# SUP_1V.net
KiCad netlist of a schematic drawn in Altium Designer
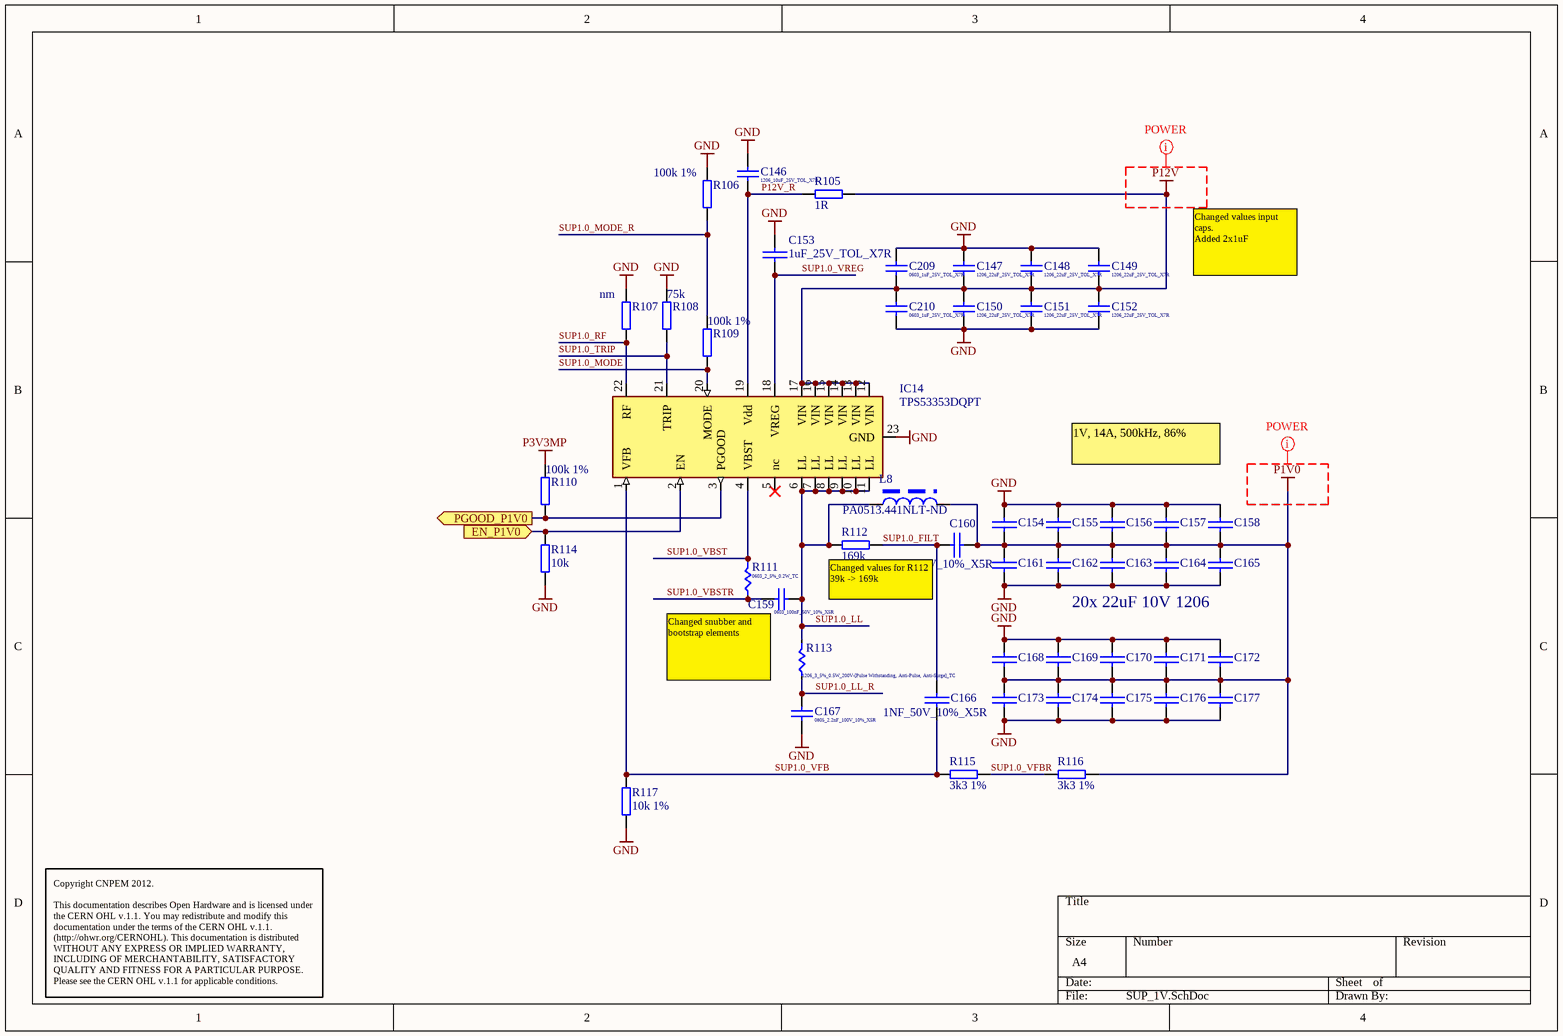
[diagram p0: SUP_1V.SchDoc]

(export (version "E")
  (design (tool "Eeschema 10.0.6"))
  (components
    (comp (ref "C146")
      (value "1206_10uF_25V_TOL_X7R")
      (footprint "CAPC3225X140N")
      (fields (field (name "PART NUMBER") "Ceramic_1206"))
      (libsource (lib "Capacitors") (part "Capacitor"))
    )
    (comp (ref "C147")
      (value "1206_22uF_25V_TOL_X7R")
      (footprint "CAPC3225X140N")
      (fields (field (name "PART NUMBER") "Ceramic_1206"))
      (libsource (lib "Capacitors") (part "Capacitor"))
    )
    (comp (ref "C148")
      (value "1206_22uF_25V_TOL_X7R")
      (footprint "CAPC3225X140N")
      (fields (field (name "PART NUMBER") "Ceramic_1206"))
      (libsource (lib "Capacitors") (part "Capacitor"))
    )
    (comp (ref "C149")
      (value "1206_22uF_25V_TOL_X7R")
      (footprint "CAPC3225X140N")
      (fields (field (name "PART NUMBER") "Ceramic_1206"))
      (libsource (lib "Capacitors") (part "Capacitor"))
    )
    (comp (ref "C150")
      (value "1206_22uF_25V_TOL_X7R")
      (footprint "CAPC3225X140N")
      (fields (field (name "PART NUMBER") "Ceramic_1206"))
      (libsource (lib "Capacitors") (part "Capacitor"))
    )
    (comp (ref "C151")
      (value "1206_22uF_25V_TOL_X7R")
      (footprint "CAPC3225X140N")
      (fields (field (name "PART NUMBER") "Ceramic_1206"))
      (libsource (lib "Capacitors") (part "Capacitor"))
    )
    (comp (ref "C152")
      (value "1206_22uF_25V_TOL_X7R")
      (footprint "CAPC3225X140N")
      (fields (field (name "PART NUMBER") "Ceramic_1206"))
      (libsource (lib "Capacitors") (part "Capacitor"))
    )
    (comp (ref "C153")
      (value "1uF_25V_TOL_X7R")
      (footprint "0603C")
      (description "Capacitor SMD")
      (libsource (lib "LIBRARY_SCH") (part "CAP_SMD_0603"))
    )
    (comp (ref "C154")
      (value "22UF_10V_10%_X7R")
      (footprint "1206C")
      (description "Capacitor SMD")
      (libsource (lib "LIBRARY_SCH") (part "CAP_SMD_1206"))
    )
    (comp (ref "C155")
      (value "22UF_10V_10%_X7R")
      (footprint "1206C")
      (description "Capacitor SMD")
      (libsource (lib "LIBRARY_SCH") (part "CAP_SMD_1206"))
    )
    (comp (ref "C156")
      (value "22UF_10V_10%_X7R")
      (footprint "1206C")
      (description "Capacitor SMD")
      (libsource (lib "LIBRARY_SCH") (part "CAP_SMD_1206"))
    )
    (comp (ref "C157")
      (value "22UF_10V_10%_X7R")
      (footprint "1206C")
      (description "Capacitor SMD")
      (libsource (lib "LIBRARY_SCH") (part "CAP_SMD_1206"))
    )
    (comp (ref "C158")
      (value "22UF_10V_10%_X7R")
      (footprint "1206C")
      (description "Capacitor SMD")
      (libsource (lib "LIBRARY_SCH") (part "CAP_SMD_1206"))
    )
    (comp (ref "C159")
      (value "0603_100nF_50V_10%_X5R")
      (footprint "CAPC1608X90N")
      (fields (field (name "PART NUMBER") "Ceramic_0603"))
      (libsource (lib "Capacitors") (part "Capacitor"))
    )
    (comp (ref "C160")
      (value "22NF_50V_10%_X5R")
      (footprint "0402C")
      (description "Capacitor SMD")
      (libsource (lib "LIBRARY_SCH") (part "CAP_SMD_0402"))
    )
    (comp (ref "C161")
      (value "22UF_10V_10%_X7R")
      (footprint "1206C")
      (description "Capacitor SMD")
      (libsource (lib "LIBRARY_SCH") (part "CAP_SMD_1206"))
    )
    (comp (ref "C162")
      (value "22UF_10V_10%_X7R")
      (footprint "1206C")
      (description "Capacitor SMD")
      (libsource (lib "LIBRARY_SCH") (part "CAP_SMD_1206"))
    )
    (comp (ref "C163")
      (value "22UF_10V_10%_X7R")
      (footprint "1206C")
      (description "Capacitor SMD")
      (libsource (lib "LIBRARY_SCH") (part "CAP_SMD_1206"))
    )
    (comp (ref "C164")
      (value "22UF_10V_10%_X7R")
      (footprint "1206C")
      (description "Capacitor SMD")
      (libsource (lib "LIBRARY_SCH") (part "CAP_SMD_1206"))
    )
    (comp (ref "C165")
      (value "22UF_10V_10%_X7R")
      (footprint "1206C")
      (description "Capacitor SMD")
      (libsource (lib "LIBRARY_SCH") (part "CAP_SMD_1206"))
    )
    (comp (ref "C166")
      (value "1NF_50V_10%_X5R")
      (footprint "0402C")
      (description "Capacitor SMD")
      (libsource (lib "LIBRARY_SCH") (part "CAP_SMD_0402"))
    )
    (comp (ref "C167")
      (value "0805_2.2nF_100V_10%_X5R")
      (footprint "CAPC2012X140N")
      (fields (field (name "PART NUMBER") "Ceramic_0805"))
      (libsource (lib "Capacitors") (part "Capacitor"))
    )
    (comp (ref "C168")
      (value "22UF_10V_10%_X7R")
      (footprint "1206C")
      (description "Capacitor SMD")
      (libsource (lib "LIBRARY_SCH") (part "CAP_SMD_1206"))
    )
    (comp (ref "C169")
      (value "22UF_10V_10%_X7R")
      (footprint "1206C")
      (description "Capacitor SMD")
      (libsource (lib "LIBRARY_SCH") (part "CAP_SMD_1206"))
    )
    (comp (ref "C170")
      (value "22UF_10V_10%_X7R")
      (footprint "1206C")
      (description "Capacitor SMD")
      (libsource (lib "LIBRARY_SCH") (part "CAP_SMD_1206"))
    )
    (comp (ref "C171")
      (value "22UF_10V_10%_X7R")
      (footprint "1206C")
      (description "Capacitor SMD")
      (libsource (lib "LIBRARY_SCH") (part "CAP_SMD_1206"))
    )
    (comp (ref "C172")
      (value "22UF_10V_10%_X7R")
      (footprint "1206C")
      (description "Capacitor SMD")
      (libsource (lib "LIBRARY_SCH") (part "CAP_SMD_1206"))
    )
    (comp (ref "C173")
      (value "22UF_10V_10%_X7R")
      (footprint "1206C")
      (description "Capacitor SMD")
      (libsource (lib "LIBRARY_SCH") (part "CAP_SMD_1206"))
    )
    (comp (ref "C174")
      (value "22UF_10V_10%_X7R")
      (footprint "1206C")
      (description "Capacitor SMD")
      (libsource (lib "LIBRARY_SCH") (part "CAP_SMD_1206"))
    )
    (comp (ref "C175")
      (value "22UF_10V_10%_X7R")
      (footprint "1206C")
      (description "Capacitor SMD")
      (libsource (lib "LIBRARY_SCH") (part "CAP_SMD_1206"))
    )
    (comp (ref "C176")
      (value "22UF_10V_10%_X7R")
      (footprint "1206C")
      (description "Capacitor SMD")
      (libsource (lib "LIBRARY_SCH") (part "CAP_SMD_1206"))
    )
    (comp (ref "C177")
      (value "22UF_10V_10%_X7R")
      (footprint "1206C")
      (description "Capacitor SMD")
      (libsource (lib "LIBRARY_SCH") (part "CAP_SMD_1206"))
    )
    (comp (ref "C209")
      (value "0603_1uF_25V_TOL_X7R")
      (footprint "CAPC1608X90N")
      (fields (field (name "PART NUMBER") "Ceramic_0603"))
      (libsource (lib "Capacitors") (part "Capacitor"))
    )
    (comp (ref "C210")
      (value "0603_1uF_25V_TOL_X7R")
      (footprint "CAPC1608X90N")
      (fields (field (name "PART NUMBER") "Ceramic_0603"))
      (libsource (lib "Capacitors") (part "Capacitor"))
    )
    (comp (ref "IC14")
      (value "TPS53353DQPT")
      (footprint "LCCS50P600X500X150-22N")
      (description "High-Efficiency 20-A Synchronous Buck Converter with Eco-mode™")
      (libsource (lib "LIBRARY_SCH") (part "PM_TPS53353"))
    )
    (comp (ref "L8")
      (value "PA0513.441NLT-ND")
      (footprint "IND_PA0513")
      (description "440nH, 30A, 0.32mOhm")
      (libsource (lib "LIBRARY_SCH") (part "L_POWER_PA1513_440nH"))
    )
    (comp (ref "R105")
      (value "1R")
      (footprint "0603R")
      (description "SMD Resistor")
      (libsource (lib "LIBRARY_SCH") (part "RES_0603"))
    )
    (comp (ref "R106")
      (value "100k 1%")
      (footprint "0603R")
      (description "SMD Resistor")
      (libsource (lib "LIBRARY_SCH") (part "RES_0603"))
    )
    (comp (ref "R107")
      (value "nm")
      (footprint "0603R")
      (description "SMD Resistor")
      (libsource (lib "LIBRARY_SCH") (part "RES_0603"))
    )
    (comp (ref "R108")
      (value "75k")
      (footprint "0603R")
      (description "SMD Resistor")
      (libsource (lib "LIBRARY_SCH") (part "RES_0603"))
    )
    (comp (ref "R109")
      (value "100k 1%")
      (footprint "0603R")
      (description "SMD Resistor")
      (libsource (lib "LIBRARY_SCH") (part "RES_0603"))
    )
    (comp (ref "R110")
      (value "100k 1%")
      (footprint "0603R")
      (description "SMD Resistor")
      (libsource (lib "LIBRARY_SCH") (part "RES_0603"))
    )
    (comp (ref "R111")
      (value "0603_2_5%_0.2W_TC")
      (footprint "RESC1608X64N")
      (fields (field (name "PART NUMBER") "SMT_0603"))
      (libsource (lib "Resistors") (part "Resistor"))
    )
    (comp (ref "R112")
      (value "169k")
      (footprint "0603R")
      (description "SMD Resistor")
      (libsource (lib "LIBRARY_SCH") (part "RES_0603"))
    )
    (comp (ref "R113")
      (value "1206_3_5%_0.5W_200V-[Pulse Withstanding, Anti-Pulse, Anti-Surge]_TC")
      (footprint "RESC3216X80N")
      (fields (field (name "PART NUMBER") "SMT_1206"))
      (libsource (lib "Resistors") (part "Resistor"))
    )
    (comp (ref "R114")
      (value "10k")
      (footprint "0402R")
      (description "SMD Resistor")
      (libsource (lib "LIBRARY_SCH") (part "RES_0402"))
    )
    (comp (ref "R115")
      (value "3k3 1%")
      (footprint "0603R")
      (description "SMD Resistor")
      (libsource (lib "LIBRARY_SCH") (part "RES_0603"))
    )
    (comp (ref "R116")
      (value "3k3 1%")
      (footprint "0603R")
      (description "SMD Resistor")
      (libsource (lib "LIBRARY_SCH") (part "RES_0603"))
    )
    (comp (ref "R117")
      (value "10k 1%")
      (footprint "0603R")
      (description "SMD Resistor")
      (libsource (lib "LIBRARY_SCH") (part "RES_0603"))
    )
  )
  (nets
    (net (code "1") (name "/EN_P1V0") (class "Default")
      (node (ref "IC14") (pin "2") (pinfunction "EN_2") (pintype "input"))
      (node (ref "R114") (pin "2") (pinfunction "2_2") (pintype "passive"))
    )
    (net (code "2") (name "/P12V_R") (class "Default")
      (node (ref "C146") (pin "1") (pinfunction "1_1") (pintype "passive"))
      (node (ref "IC14") (pin "19") (pinfunction "Vdd_19") (pintype "power_in"))
      (node (ref "R105") (pin "2") (pinfunction "2_2") (pintype "passive"))
    )
    (net (code "3") (name "/PGOOD_P1V0") (class "Default")
      (node (ref "IC14") (pin "3") (pinfunction "PGOOD_3") (pintype "output"))
      (node (ref "R110") (pin "1") (pinfunction "1_1") (pintype "passive"))
    )
    (net (code "4") (name "/SUP1.0_FILT") (class "Default")
      (node (ref "C160") (pin "1") (pinfunction "1_1") (pintype "passive"))
      (node (ref "C166") (pin "2") (pinfunction "2_2") (pintype "passive"))
      (node (ref "R112") (pin "1") (pinfunction "1_1") (pintype "passive"))
    )
    (net (code "5") (name "/SUP1.0_LL") (class "Default")
      (node (ref "C159") (pin "1") (pinfunction "1_1") (pintype "passive"))
      (node (ref "IC14") (pin "10") (pinfunction "LL_10") (pintype "passive"))
      (node (ref "IC14") (pin "11") (pinfunction "LL_11") (pintype "passive"))
      (node (ref "IC14") (pin "6") (pinfunction "LL_6") (pintype "passive"))
      (node (ref "IC14") (pin "7") (pinfunction "LL_7") (pintype "passive"))
      (node (ref "IC14") (pin "8") (pinfunction "LL_8") (pintype "passive"))
      (node (ref "IC14") (pin "9") (pinfunction "LL_9") (pintype "passive"))
      (node (ref "L8") (pin "1") (pintype "passive"))
      (node (ref "R112") (pin "2") (pinfunction "2_2") (pintype "passive"))
      (node (ref "R113") (pin "1") (pinfunction "+_1") (pintype "passive"))
    )
    (net (code "6") (name "/SUP1.0_LL_R") (class "Default")
      (node (ref "C167") (pin "2") (pinfunction "2_2") (pintype "passive"))
      (node (ref "R113") (pin "2") (pinfunction "-_2") (pintype "passive"))
    )
    (net (code "7") (name "/SUP1.0_MODE") (class "Default")
      (node (ref "IC14") (pin "20") (pinfunction "MODE_20") (pintype "input"))
      (node (ref "R109") (pin "1") (pinfunction "1_1") (pintype "passive"))
    )
    (net (code "8") (name "/SUP1.0_MODE_R") (class "Default")
      (node (ref "R106") (pin "1") (pinfunction "1_1") (pintype "passive"))
      (node (ref "R109") (pin "2") (pinfunction "2_2") (pintype "passive"))
    )
    (net (code "9") (name "/SUP1.0_RF") (class "Default")
      (node (ref "IC14") (pin "22") (pinfunction "RF_22") (pintype "passive"))
      (node (ref "R107") (pin "1") (pinfunction "1_1") (pintype "passive"))
    )
    (net (code "10") (name "/SUP1.0_TRIP") (class "Default")
      (node (ref "IC14") (pin "21") (pinfunction "TRIP_21") (pintype "passive"))
      (node (ref "R108") (pin "1") (pinfunction "1_1") (pintype "passive"))
    )
    (net (code "11") (name "/SUP1.0_VBST") (class "Default")
      (node (ref "IC14") (pin "4") (pinfunction "VBST_4") (pintype "passive"))
      (node (ref "R111") (pin "1") (pinfunction "+_1") (pintype "passive"))
    )
    (net (code "12") (name "/SUP1.0_VBSTR") (class "Default")
      (node (ref "C159") (pin "2") (pinfunction "2_2") (pintype "passive"))
      (node (ref "R111") (pin "2") (pinfunction "-_2") (pintype "passive"))
    )
    (net (code "13") (name "/SUP1.0_VFB") (class "Default")
      (node (ref "C166") (pin "1") (pinfunction "1_1") (pintype "passive"))
      (node (ref "IC14") (pin "1") (pinfunction "VFB_1") (pintype "input"))
      (node (ref "R115") (pin "1") (pinfunction "1_1") (pintype "passive"))
      (node (ref "R117") (pin "1") (pinfunction "1_1") (pintype "passive"))
    )
    (net (code "14") (name "/SUP1.0_VFBR") (class "Default")
      (node (ref "R115") (pin "2") (pinfunction "2_2") (pintype "passive"))
      (node (ref "R116") (pin "1") (pinfunction "1_1") (pintype "passive"))
    )
    (net (code "15") (name "/SUP1.0_VREG") (class "Default")
      (node (ref "C153") (pin "2") (pinfunction "2_2") (pintype "passive"))
      (node (ref "IC14") (pin "18") (pinfunction "VREG_18") (pintype "power_in"))
    )
    (net (code "16") (name "GND") (class "Default")
      (node (ref "C146") (pin "2") (pinfunction "2_2") (pintype "passive"))
      (node (ref "C147") (pin "2") (pinfunction "2_2") (pintype "passive"))
      (node (ref "C148") (pin "2") (pinfunction "2_2") (pintype "passive"))
      (node (ref "C149") (pin "2") (pinfunction "2_2") (pintype "passive"))
      (node (ref "C150") (pin "1") (pinfunction "1_1") (pintype "passive"))
      (node (ref "C151") (pin "1") (pinfunction "1_1") (pintype "passive"))
      (node (ref "C152") (pin "1") (pinfunction "1_1") (pintype "passive"))
      (node (ref "C153") (pin "1") (pinfunction "1_1") (pintype "passive"))
      (node (ref "C154") (pin "1") (pinfunction "1_1") (pintype "passive"))
      (node (ref "C155") (pin "1") (pinfunction "1_1") (pintype "passive"))
      (node (ref "C156") (pin "1") (pinfunction "1_1") (pintype "passive"))
      (node (ref "C157") (pin "1") (pinfunction "1_1") (pintype "passive"))
      (node (ref "C158") (pin "1") (pinfunction "1_1") (pintype "passive"))
      (node (ref "C161") (pin "2") (pinfunction "2_2") (pintype "passive"))
      (node (ref "C162") (pin "2") (pinfunction "2_2") (pintype "passive"))
      (node (ref "C163") (pin "2") (pinfunction "2_2") (pintype "passive"))
      (node (ref "C164") (pin "2") (pinfunction "2_2") (pintype "passive"))
      (node (ref "C165") (pin "2") (pinfunction "2_2") (pintype "passive"))
      (node (ref "C167") (pin "1") (pinfunction "1_1") (pintype "passive"))
      (node (ref "C168") (pin "1") (pinfunction "1_1") (pintype "passive"))
      (node (ref "C169") (pin "1") (pinfunction "1_1") (pintype "passive"))
      (node (ref "C170") (pin "1") (pinfunction "1_1") (pintype "passive"))
      (node (ref "C171") (pin "1") (pinfunction "1_1") (pintype "passive"))
      (node (ref "C172") (pin "1") (pinfunction "1_1") (pintype "passive"))
      (node (ref "C173") (pin "2") (pinfunction "2_2") (pintype "passive"))
      (node (ref "C174") (pin "2") (pinfunction "2_2") (pintype "passive"))
      (node (ref "C175") (pin "2") (pinfunction "2_2") (pintype "passive"))
      (node (ref "C176") (pin "2") (pinfunction "2_2") (pintype "passive"))
      (node (ref "C177") (pin "2") (pinfunction "2_2") (pintype "passive"))
      (node (ref "C209") (pin "2") (pinfunction "2_2") (pintype "passive"))
      (node (ref "C210") (pin "1") (pinfunction "1_1") (pintype "passive"))
      (node (ref "IC14") (pin "23") (pinfunction "GND_23") (pintype "power_in"))
      (node (ref "R106") (pin "2") (pinfunction "2_2") (pintype "passive"))
      (node (ref "R107") (pin "2") (pinfunction "2_2") (pintype "passive"))
      (node (ref "R108") (pin "2") (pinfunction "2_2") (pintype "passive"))
      (node (ref "R114") (pin "1") (pinfunction "1_1") (pintype "passive"))
      (node (ref "R117") (pin "2") (pinfunction "2_2") (pintype "passive"))
    )
    (net (code "17") (name "P1V0") (class "Default")
      (node (ref "C154") (pin "2") (pinfunction "2_2") (pintype "passive"))
      (node (ref "C155") (pin "2") (pinfunction "2_2") (pintype "passive"))
      (node (ref "C156") (pin "2") (pinfunction "2_2") (pintype "passive"))
      (node (ref "C157") (pin "2") (pinfunction "2_2") (pintype "passive"))
      (node (ref "C158") (pin "2") (pinfunction "2_2") (pintype "passive"))
      (node (ref "C160") (pin "2") (pinfunction "2_2") (pintype "passive"))
      (node (ref "C161") (pin "1") (pinfunction "1_1") (pintype "passive"))
      (node (ref "C162") (pin "1") (pinfunction "1_1") (pintype "passive"))
      (node (ref "C163") (pin "1") (pinfunction "1_1") (pintype "passive"))
      (node (ref "C164") (pin "1") (pinfunction "1_1") (pintype "passive"))
      (node (ref "C165") (pin "1") (pinfunction "1_1") (pintype "passive"))
      (node (ref "C168") (pin "2") (pinfunction "2_2") (pintype "passive"))
      (node (ref "C169") (pin "2") (pinfunction "2_2") (pintype "passive"))
      (node (ref "C170") (pin "2") (pinfunction "2_2") (pintype "passive"))
      (node (ref "C171") (pin "2") (pinfunction "2_2") (pintype "passive"))
      (node (ref "C172") (pin "2") (pinfunction "2_2") (pintype "passive"))
      (node (ref "C173") (pin "1") (pinfunction "1_1") (pintype "passive"))
      (node (ref "C174") (pin "1") (pinfunction "1_1") (pintype "passive"))
      (node (ref "C175") (pin "1") (pinfunction "1_1") (pintype "passive"))
      (node (ref "C176") (pin "1") (pinfunction "1_1") (pintype "passive"))
      (node (ref "C177") (pin "1") (pinfunction "1_1") (pintype "passive"))
      (node (ref "L8") (pin "2") (pintype "passive"))
      (node (ref "R116") (pin "2") (pinfunction "2_2") (pintype "passive"))
    )
    (net (code "18") (name "P3V3MP") (class "Default")
      (node (ref "R110") (pin "2") (pinfunction "2_2") (pintype "passive"))
    )
    (net (code "19") (name "P12V") (class "Default")
      (node (ref "C147") (pin "1") (pinfunction "1_1") (pintype "passive"))
      (node (ref "C148") (pin "1") (pinfunction "1_1") (pintype "passive"))
      (node (ref "C149") (pin "1") (pinfunction "1_1") (pintype "passive"))
      (node (ref "C150") (pin "2") (pinfunction "2_2") (pintype "passive"))
      (node (ref "C151") (pin "2") (pinfunction "2_2") (pintype "passive"))
      (node (ref "C152") (pin "2") (pinfunction "2_2") (pintype "passive"))
      (node (ref "C209") (pin "1") (pinfunction "1_1") (pintype "passive"))
      (node (ref "C210") (pin "2") (pinfunction "2_2") (pintype "passive"))
      (node (ref "IC14") (pin "12") (pinfunction "VIN_12") (pintype "power_in"))
      (node (ref "IC14") (pin "13") (pinfunction "VIN_13") (pintype "power_in"))
      (node (ref "IC14") (pin "14") (pinfunction "VIN_14") (pintype "power_in"))
      (node (ref "IC14") (pin "15") (pinfunction "VIN_15") (pintype "power_in"))
      (node (ref "IC14") (pin "16") (pinfunction "VIN_16") (pintype "power_in"))
      (node (ref "IC14") (pin "17") (pinfunction "VIN_17") (pintype "power_in"))
      (node (ref "R105") (pin "1") (pinfunction "1_1") (pintype "passive"))
    )
    (net (code "20") (name "unconnected-(IC14-nc-Pad5)") (class "Default")
      (node (ref "IC14") (pin "5") (pinfunction "nc_5") (pintype "passive+no_connect"))
    )
  )
)
